# Temperature_Sensor_Rev_5.net
KiCad netlist of a schematic drawn in EAGLE
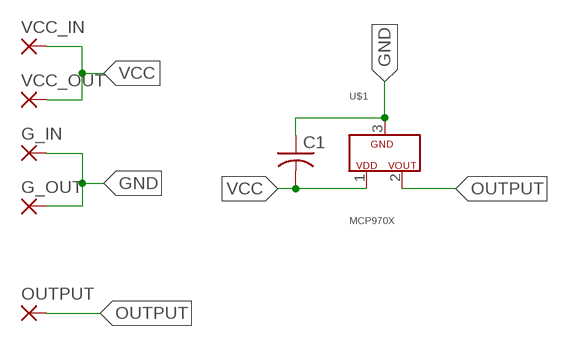
[diagram p0: schematic, sheet 1]

(export (version "E")
  (design (tool "Eeschema 10.0.6"))
  (components
    (comp (ref "C1")
      (value "C-USC0603")
      (footprint "eagle-import:C0603")
      (libsource (lib "eagle-import") (part "C-USC0603"))
    )
    (comp (ref "G_IN")
      (value "1,6/0,8")
      (footprint "eagle-import:1,6_0,8")
      (libsource (lib "eagle-import") (part "1,6/0,8"))
    )
    (comp (ref "G_OUT")
      (value "1,6/0,8")
      (footprint "eagle-import:1,6_0,8")
      (libsource (lib "eagle-import") (part "1,6/0,8"))
    )
    (comp (ref "OUTPUT")
      (value "1,6/0,8")
      (footprint "eagle-import:1,6_0,8")
      (libsource (lib "eagle-import") (part "1,6/0,8"))
    )
    (comp (ref "U$1")
      (value "MCP970X")
      (footprint "eagle-import:SOT23")
      (libsource (lib "eagle-import") (part "MCP970X"))
    )
    (comp (ref "VCC_IN")
      (value "1,6/0,8")
      (footprint "eagle-import:1,6_0,8")
      (libsource (lib "eagle-import") (part "1,6/0,8"))
    )
    (comp (ref "VCC_OUT")
      (value "1,6/0,8")
      (footprint "eagle-import:1,6_0,8")
      (libsource (lib "eagle-import") (part "1,6/0,8"))
    )
  )
  (nets
    (net (code "1") (name "GND") (class "Default")
      (node (ref "C1") (pin "1") (pinfunction "1_1") (pintype "passive"))
      (node (ref "G_IN") (pin "1") (pinfunction "P_1") (pintype "passive"))
      (node (ref "G_OUT") (pin "1") (pinfunction "P_1") (pintype "passive"))
      (node (ref "U$1") (pin "3") (pinfunction "GND_3") (pintype "bidirectional"))
    )
    (net (code "2") (name "OUTPUT") (class "Default")
      (node (ref "OUTPUT") (pin "1") (pinfunction "P_1") (pintype "passive"))
      (node (ref "U$1") (pin "2") (pinfunction "VOUT_2") (pintype "bidirectional"))
    )
    (net (code "3") (name "VCC") (class "Default")
      (node (ref "C1") (pin "2") (pinfunction "2_2") (pintype "passive"))
      (node (ref "U$1") (pin "1") (pinfunction "VDD_1") (pintype "bidirectional"))
      (node (ref "VCC_IN") (pin "1") (pinfunction "P_1") (pintype "passive"))
      (node (ref "VCC_OUT") (pin "1") (pinfunction "P_1") (pintype "passive"))
    )
  )
)
